# Safe_Cracker_Shield.net
KiCad netlist of a schematic drawn in EAGLE
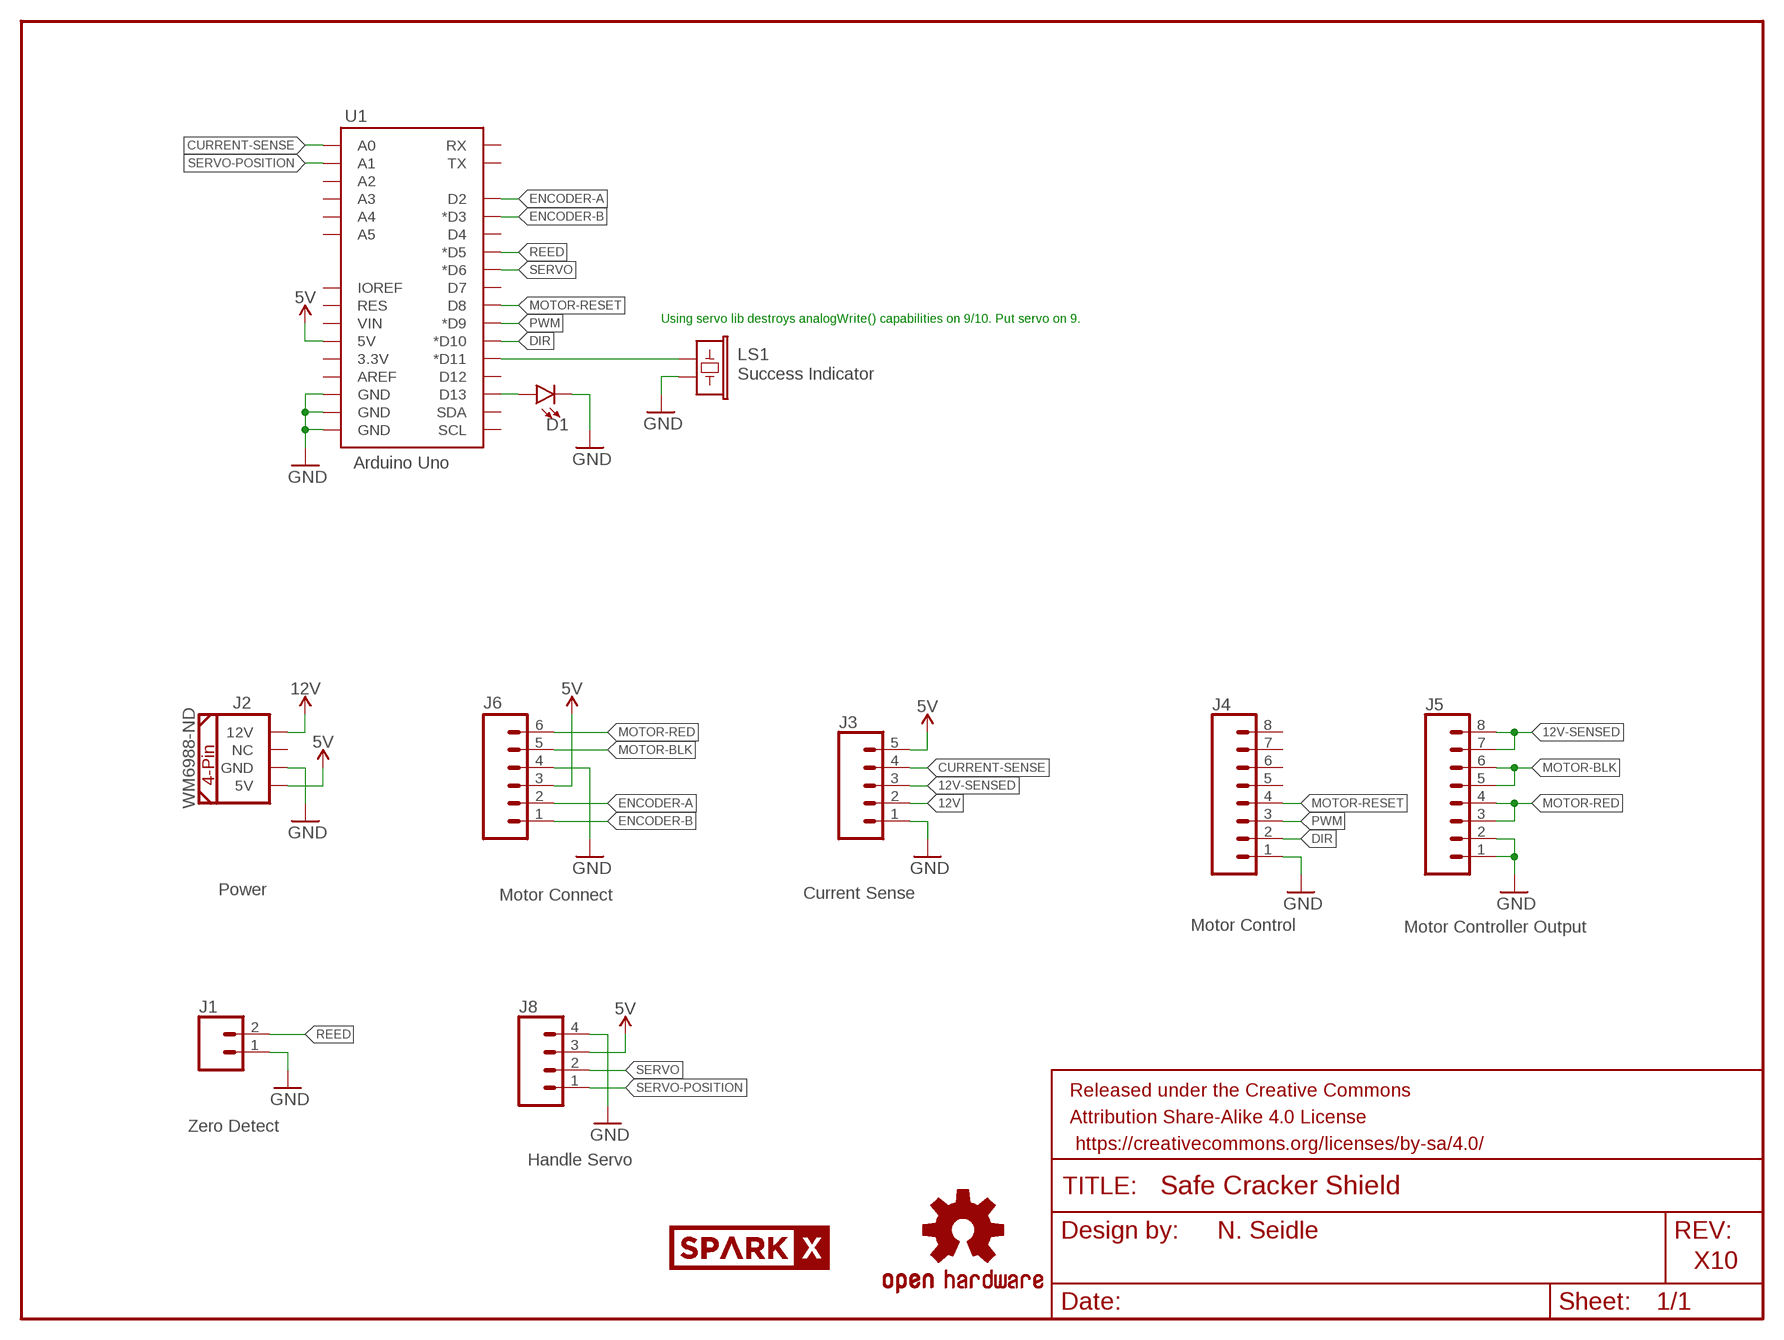
[diagram p0: schematic, sheet 1]

(export (version "E")
  (design (tool "Eeschema 10.0.6"))
  (components
    (comp (ref "D1")
      (value "LED5MM")
      (footprint "eagle-import:LED_5MM")
      (libsource (lib "eagle-import") (part "LED5MM"))
    )
    (comp (ref "FRAME1")
      (value "FRAME-LETTER")
      (footprint "eagle-import:CREATIVE_COMMONS")
      (libsource (lib "eagle-import") (part "FRAME-LETTER"))
    )
    (comp (ref "J1")
      (value "Zero Detect")
      (footprint "eagle-import:JST-2-PTH")
      (libsource (lib "eagle-import") (part "CONN_02JST-PTH-2"))
    )
    (comp (ref "J2")
      (value "Power")
      (footprint "eagle-import:COMPUTER-PERIPHERAL-POWER-RA")
      (libsource (lib "eagle-import") (part "COMPUTER-PERIPHERAL-POWERRA"))
    )
    (comp (ref "J3")
      (value "Current Sense")
      (footprint "eagle-import:1X05")
      (libsource (lib "eagle-import") (part "CONN_05"))
    )
    (comp (ref "J4")
      (value "Motor Control")
      (footprint "eagle-import:1X08")
      (libsource (lib "eagle-import") (part "CONN_08{dblquote}"))
    )
    (comp (ref "J5")
      (value "Motor Controller Output")
      (footprint "eagle-import:1X08")
      (libsource (lib "eagle-import") (part "CONN_08{dblquote}"))
    )
    (comp (ref "J6")
      (value "Motor Connect")
      (footprint "eagle-import:1X06")
      (libsource (lib "eagle-import") (part "M06SILK_FEMALE_PTH"))
    )
    (comp (ref "J8")
      (value "Handle Servo")
      (footprint "eagle-import:1X04")
      (libsource (lib "eagle-import") (part "CONN_04"))
    )
    (comp (ref "LOGO2")
      (value "OSHW-LOGOS")
      (footprint "eagle-import:OSHW-LOGO-S")
      (libsource (lib "eagle-import") (part "OSHW-LOGOS"))
    )
    (comp (ref "LS1")
      (value "Success Indicator")
      (footprint "eagle-import:BUZZER-12MM")
      (libsource (lib "eagle-import") (part "BUZZER-PTH"))
    )
    (comp (ref "U$1")
      (value "SPARKX-LOGO4")
      (footprint "eagle-import:SPARKX-MEDIUM")
      (libsource (lib "eagle-import") (part "SPARKX-LOGO4"))
    )
    (comp (ref "U1")
      (value "Arduino Uno")
      (footprint "eagle-import:UNO_R3_SHIELD_NOLABELS")
      (libsource (lib "eagle-import") (part "ARDUINO_R3_SHIELDNOLABELS"))
    )
  )
  (nets
    (net (code "1") (name "5V") (class "Default")
      (node (ref "J2") (pin "5V") (pinfunction "5V_5V") (pintype "passive"))
      (node (ref "J3") (pin "5") (pinfunction "5_5") (pintype "passive"))
      (node (ref "J6") (pin "3") (pinfunction "3_3") (pintype "passive"))
      (node (ref "J8") (pin "3") (pinfunction "3_3") (pintype "passive"))
      (node (ref "U1") (pin "5V") (pinfunction "5V_5V") (pintype "bidirectional"))
    )
    (net (code "2") (name "12V") (class "Default")
      (node (ref "J2") (pin "12V") (pinfunction "12V_12V") (pintype "passive"))
      (node (ref "J3") (pin "2") (pinfunction "2_2") (pintype "passive"))
    )
    (net (code "3") (name "12V-SENSED") (class "Default")
      (node (ref "J3") (pin "3") (pinfunction "3_3") (pintype "passive"))
      (node (ref "J5") (pin "7") (pinfunction "7_7") (pintype "passive"))
      (node (ref "J5") (pin "8") (pinfunction "8_8") (pintype "passive"))
    )
    (net (code "4") (name "CURRENT-SENSE") (class "Default")
      (node (ref "J3") (pin "4") (pinfunction "4_4") (pintype "passive"))
      (node (ref "U1") (pin "A0") (pinfunction "A0_A0") (pintype "bidirectional"))
    )
    (net (code "5") (name "DIR") (class "Default")
      (node (ref "J4") (pin "2") (pinfunction "2_2") (pintype "passive"))
      (node (ref "U1") (pin "D10") (pinfunction "*D10_D10") (pintype "bidirectional"))
    )
    (net (code "6") (name "ENCODER-A") (class "Default")
      (node (ref "J6") (pin "2") (pinfunction "2_2") (pintype "passive"))
      (node (ref "U1") (pin "D2") (pinfunction "D2_D2") (pintype "bidirectional"))
    )
    (net (code "7") (name "ENCODER-B") (class "Default")
      (node (ref "J6") (pin "1") (pinfunction "1_1") (pintype "passive"))
      (node (ref "U1") (pin "D3") (pinfunction "*D3_D3") (pintype "bidirectional"))
    )
    (net (code "8") (name "GND") (class "Default")
      (node (ref "D1") (pin "K") (pinfunction "C_K") (pintype "passive"))
      (node (ref "J1") (pin "1") (pinfunction "1_1") (pintype "passive"))
      (node (ref "J2") (pin "GND") (pinfunction "GND_GND") (pintype "passive"))
      (node (ref "J3") (pin "1") (pinfunction "1_1") (pintype "passive"))
      (node (ref "J4") (pin "1") (pinfunction "1_1") (pintype "passive"))
      (node (ref "J5") (pin "1") (pinfunction "1_1") (pintype "passive"))
      (node (ref "J5") (pin "2") (pinfunction "2_2") (pintype "passive"))
      (node (ref "J6") (pin "4") (pinfunction "4_4") (pintype "passive"))
      (node (ref "J8") (pin "4") (pinfunction "4_4") (pintype "passive"))
      (node (ref "LS1") (pin "-") (pinfunction "2_-") (pintype "passive"))
      (node (ref "U1") (pin "GND@0") (pinfunction "GND_GND@0") (pintype "bidirectional"))
      (node (ref "U1") (pin "GND@1") (pinfunction "GND_GND@1") (pintype "bidirectional"))
      (node (ref "U1") (pin "GND@2") (pinfunction "GND_GND@2") (pintype "bidirectional"))
    )
    (net (code "9") (name "MOTOR-BLK") (class "Default")
      (node (ref "J5") (pin "5") (pinfunction "5_5") (pintype "passive"))
      (node (ref "J5") (pin "6") (pinfunction "6_6") (pintype "passive"))
      (node (ref "J6") (pin "5") (pinfunction "5_5") (pintype "passive"))
    )
    (net (code "10") (name "MOTOR-RED") (class "Default")
      (node (ref "J5") (pin "3") (pinfunction "3_3") (pintype "passive"))
      (node (ref "J5") (pin "4") (pinfunction "4_4") (pintype "passive"))
      (node (ref "J6") (pin "6") (pinfunction "6_6") (pintype "passive"))
    )
    (net (code "11") (name "MOTOR-RESET") (class "Default")
      (node (ref "J4") (pin "4") (pinfunction "4_4") (pintype "passive"))
      (node (ref "U1") (pin "D8") (pinfunction "D8_D8") (pintype "bidirectional"))
    )
    (net (code "12") (name "Net-(D1-PadA)") (class "Default")
      (node (ref "D1") (pin "A") (pinfunction "A_A") (pintype "passive"))
      (node (ref "U1") (pin "D13") (pinfunction "D13_D13") (pintype "bidirectional"))
    )
    (net (code "13") (name "Net-(LS1-1)") (class "Default")
      (node (ref "LS1") (pin "+") (pinfunction "1_+") (pintype "passive"))
      (node (ref "U1") (pin "D11") (pinfunction "*D11_D11") (pintype "bidirectional"))
    )
    (net (code "14") (name "PWM") (class "Default")
      (node (ref "J4") (pin "3") (pinfunction "3_3") (pintype "passive"))
      (node (ref "U1") (pin "D9") (pinfunction "*D9_D9") (pintype "bidirectional"))
    )
    (net (code "15") (name "REED") (class "Default")
      (node (ref "J1") (pin "2") (pinfunction "2_2") (pintype "passive"))
      (node (ref "U1") (pin "D5") (pinfunction "*D5_D5") (pintype "bidirectional"))
    )
    (net (code "16") (name "SERVO") (class "Default")
      (node (ref "J8") (pin "2") (pinfunction "2_2") (pintype "passive"))
      (node (ref "U1") (pin "D6") (pinfunction "*D6_D6") (pintype "bidirectional"))
    )
    (net (code "17") (name "SERVO-POSITION") (class "Default")
      (node (ref "J8") (pin "1") (pinfunction "1_1") (pintype "passive"))
      (node (ref "U1") (pin "A1") (pinfunction "A1_A1") (pintype "bidirectional"))
    )
    (net (code "18") (name "unconnected-(J2-PadNC)") (class "Default")
      (node (ref "J2") (pin "NC") (pinfunction "NC_NC") (pintype "passive"))
    )
    (net (code "19") (name "unconnected-(J4-Pad5)") (class "Default")
      (node (ref "J4") (pin "5") (pinfunction "5_5") (pintype "passive"))
    )
    (net (code "20") (name "unconnected-(J4-Pad6)") (class "Default")
      (node (ref "J4") (pin "6") (pinfunction "6_6") (pintype "passive"))
    )
    (net (code "21") (name "unconnected-(J4-Pad7)") (class "Default")
      (node (ref "J4") (pin "7") (pinfunction "7_7") (pintype "passive"))
    )
    (net (code "22") (name "unconnected-(J4-Pad8)") (class "Default")
      (node (ref "J4") (pin "8") (pinfunction "8_8") (pintype "passive"))
    )
    (net (code "23") (name "unconnected-(U1-Pad3.3V)") (class "Default")
      (node (ref "U1") (pin "3.3V") (pinfunction "3.3V_3.3V") (pintype "bidirectional"))
    )
    (net (code "24") (name "unconnected-(U1-PadA2)") (class "Default")
      (node (ref "U1") (pin "A2") (pinfunction "A2_A2") (pintype "bidirectional"))
    )
    (net (code "25") (name "unconnected-(U1-PadA3)") (class "Default")
      (node (ref "U1") (pin "A3") (pinfunction "A3_A3") (pintype "bidirectional"))
    )
    (net (code "26") (name "unconnected-(U1-PadA4)") (class "Default")
      (node (ref "U1") (pin "A4") (pinfunction "A4_A4") (pintype "bidirectional"))
    )
    (net (code "27") (name "unconnected-(U1-PadA5)") (class "Default")
      (node (ref "U1") (pin "A5") (pinfunction "A5_A5") (pintype "bidirectional"))
    )
    (net (code "28") (name "unconnected-(U1-PadAREF)") (class "Default")
      (node (ref "U1") (pin "AREF") (pinfunction "AREF_AREF") (pintype "bidirectional"))
    )
    (net (code "29") (name "unconnected-(U1-PadD4)") (class "Default")
      (node (ref "U1") (pin "D4") (pinfunction "D4_D4") (pintype "bidirectional"))
    )
    (net (code "30") (name "unconnected-(U1-PadD7)") (class "Default")
      (node (ref "U1") (pin "D7") (pinfunction "D7_D7") (pintype "bidirectional"))
    )
    (net (code "31") (name "unconnected-(U1-PadD12)") (class "Default")
      (node (ref "U1") (pin "D12") (pinfunction "D12_D12") (pintype "bidirectional"))
    )
    (net (code "32") (name "unconnected-(U1-PadIOREF)") (class "Default")
      (node (ref "U1") (pin "IOREF") (pinfunction "IOREF_IOREF") (pintype "bidirectional"))
    )
    (net (code "33") (name "unconnected-(U1-PadRES)") (class "Default")
      (node (ref "U1") (pin "RES") (pinfunction "RES_RES") (pintype "bidirectional"))
    )
    (net (code "34") (name "unconnected-(U1-PadRX)") (class "Default")
      (node (ref "U1") (pin "RX") (pinfunction "RX_RX") (pintype "bidirectional"))
    )
    (net (code "35") (name "unconnected-(U1-PadSCL)") (class "Default")
      (node (ref "U1") (pin "SCL") (pinfunction "SCL_SCL") (pintype "bidirectional"))
    )
    (net (code "36") (name "unconnected-(U1-PadSDA)") (class "Default")
      (node (ref "U1") (pin "SDA") (pinfunction "SDA_SDA") (pintype "bidirectional"))
    )
    (net (code "37") (name "unconnected-(U1-PadTX)") (class "Default")
      (node (ref "U1") (pin "TX") (pinfunction "TX_TX") (pintype "bidirectional"))
    )
    (net (code "38") (name "unconnected-(U1-PadVIN)") (class "Default")
      (node (ref "U1") (pin "VIN") (pinfunction "VIN_VIN") (pintype "bidirectional"))
    )
  )
)
